# LDC10.net
KiCad netlist of a schematic drawn in Altium Designer
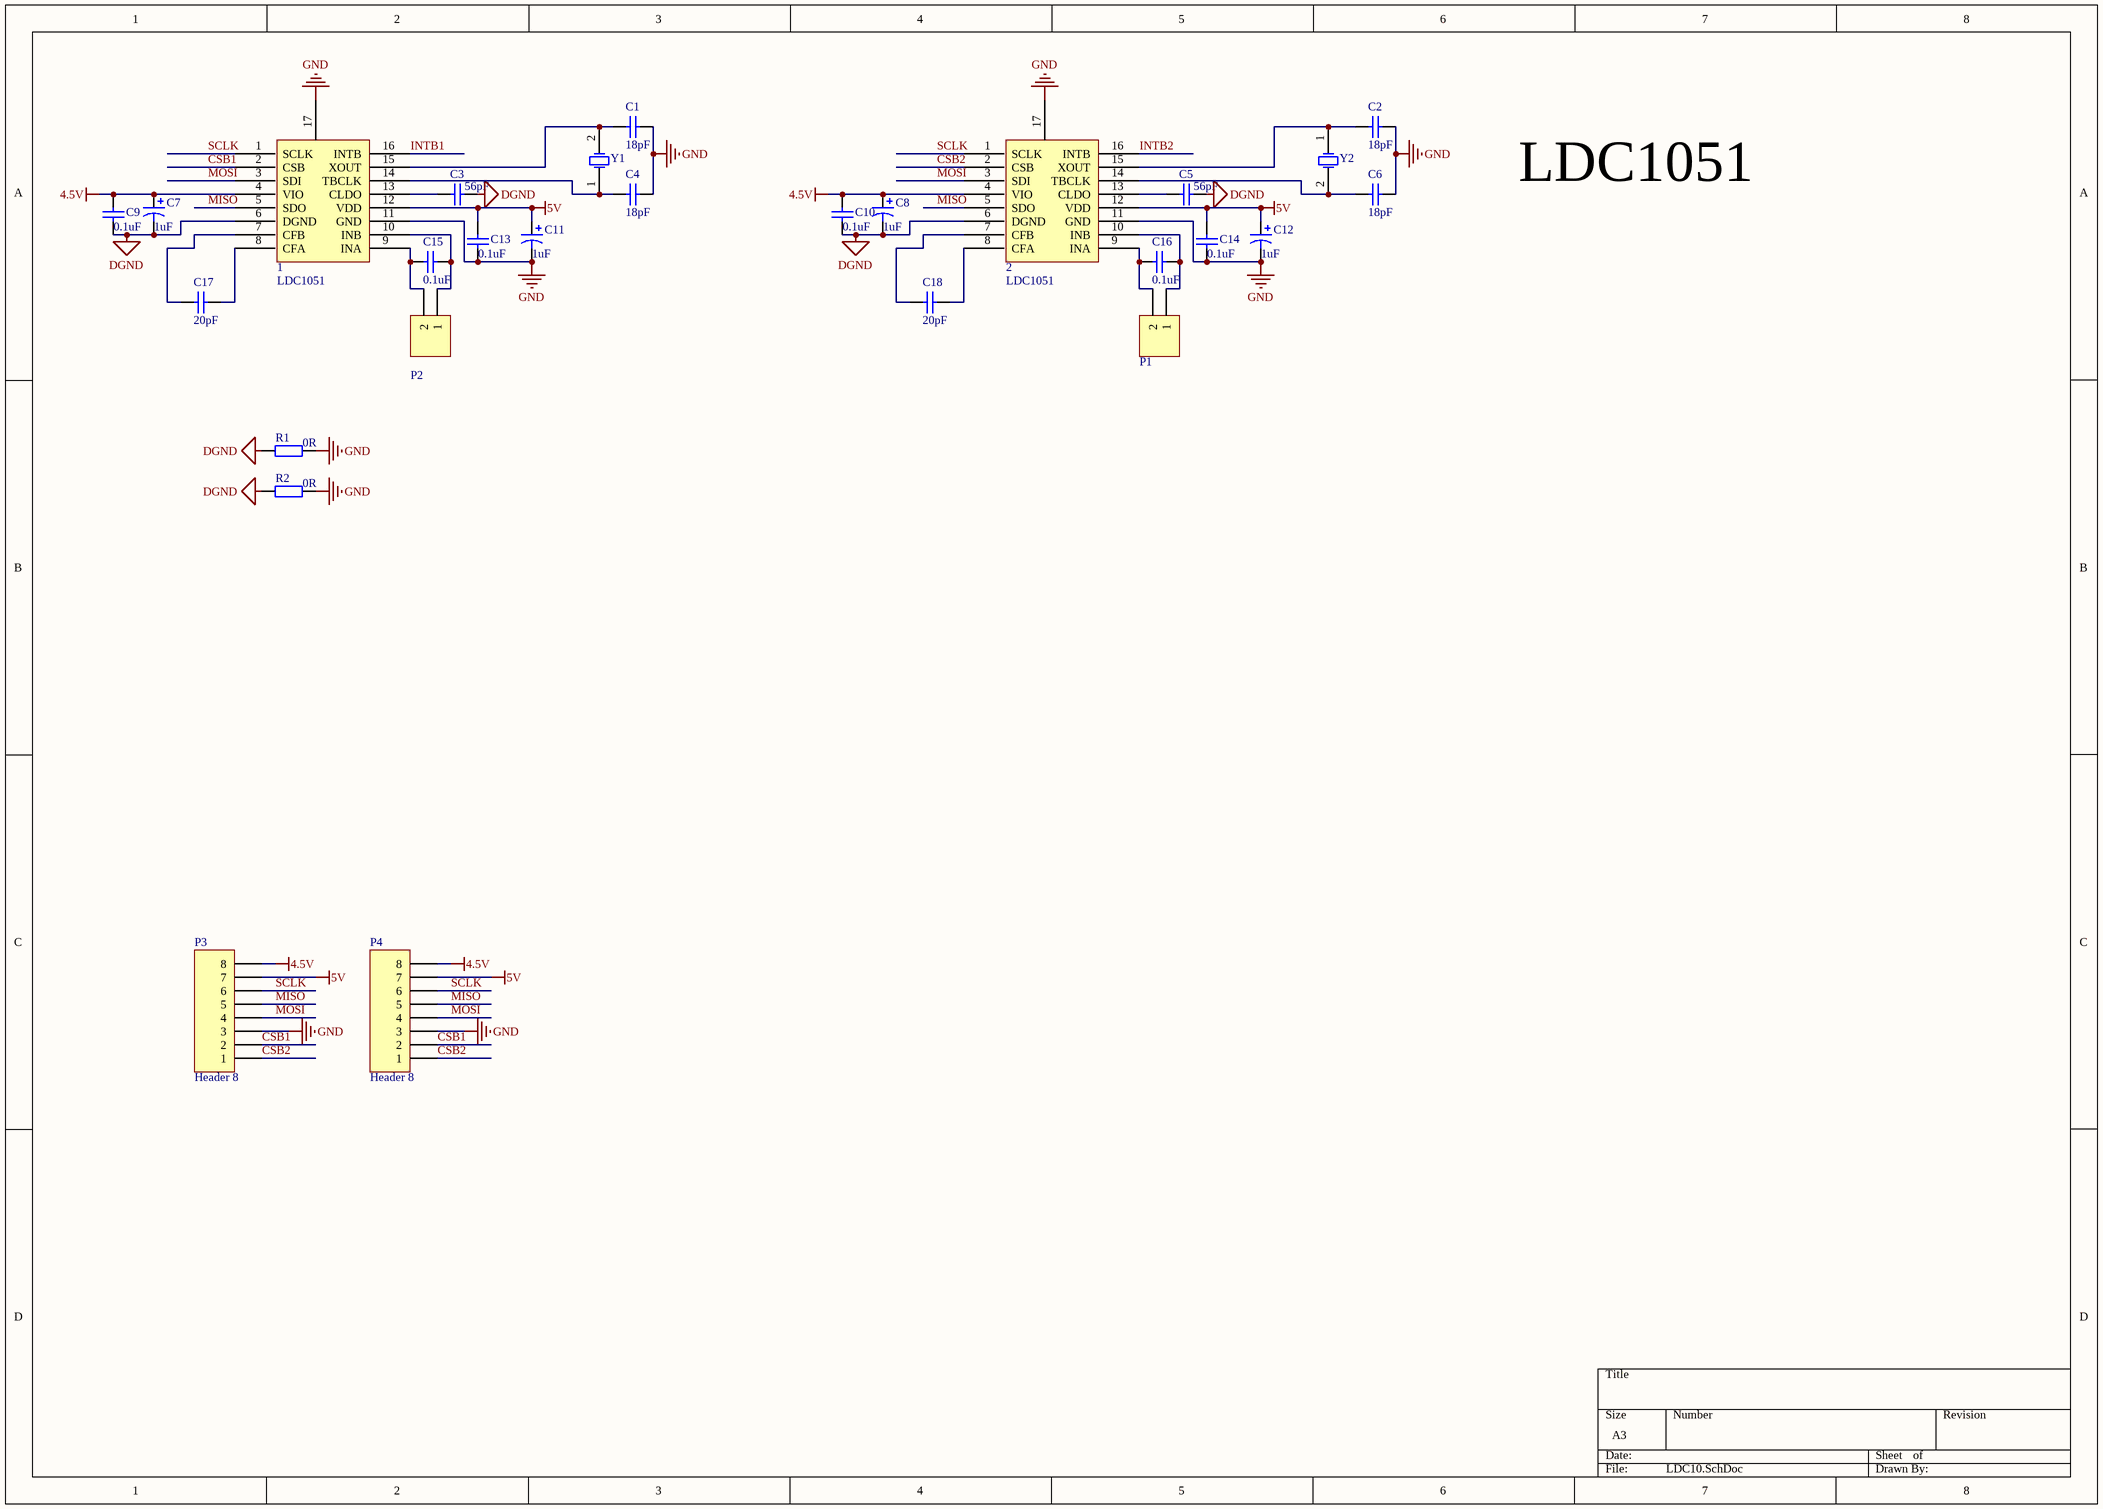
[diagram p0: LDC10.SchDoc]

(export (version "E")
  (design (tool "Eeschema 10.0.6"))
  (components
    (comp (ref "1") (value "LDC1051") (footprint "LDC1000") (libsource (lib "原理图") (part "LDC1000")))
    (comp (ref "2") (value "LDC1051") (footprint "LDC1000") (libsource (lib "原理图") (part "LDC1000")))
    (comp (ref "C1")
      (value "18pF")
      (footprint "C2012")
      (description "Capacitor")
      (fields (field (name "Comment") "Cap") (field (name "PUBLISHER") "Altium Limited"))
      (libsource (lib "Miscellaneous Devices") (part "Cap"))
    )
    (comp (ref "C2")
      (value "18pF")
      (footprint "C2012")
      (description "Capacitor")
      (fields (field (name "Comment") "Cap") (field (name "PUBLISHER") "Altium Limited"))
      (libsource (lib "Miscellaneous Devices") (part "Cap"))
    )
    (comp (ref "C3")
      (value "56pF")
      (footprint "C2012")
      (description "Capacitor")
      (fields (field (name "Comment") "Cap") (field (name "PUBLISHER") "Altium Limited"))
      (libsource (lib "Miscellaneous Devices") (part "Cap"))
    )
    (comp (ref "C4")
      (value "18pF")
      (footprint "C2012")
      (description "Capacitor")
      (fields (field (name "Comment") "Cap") (field (name "PUBLISHER") "Altium Limited"))
      (libsource (lib "Miscellaneous Devices") (part "Cap"))
    )
    (comp (ref "C5")
      (value "56pF")
      (footprint "C2012")
      (description "Capacitor")
      (fields (field (name "Comment") "Cap") (field (name "PUBLISHER") "Altium Limited"))
      (libsource (lib "Miscellaneous Devices") (part "Cap"))
    )
    (comp (ref "C6")
      (value "18pF")
      (footprint "C2012")
      (description "Capacitor")
      (fields (field (name "Comment") "Cap") (field (name "PUBLISHER") "Altium Limited"))
      (libsource (lib "Miscellaneous Devices") (part "Cap"))
    )
    (comp (ref "C7")
      (value "1uF")
      (footprint "C2012")
      (description "Polarized Capacitor (Radial)")
      (fields (field (name "Comment") "Cap Pol1") (field (name "PUBLISHER") "Altium Limited"))
      (libsource (lib "Miscellaneous Devices") (part "Cap Pol1"))
    )
    (comp (ref "C8")
      (value "1uF")
      (footprint "C2012")
      (description "Polarized Capacitor (Radial)")
      (fields (field (name "Comment") "Cap Pol1") (field (name "PUBLISHER") "Altium Limited"))
      (libsource (lib "Miscellaneous Devices") (part "Cap Pol1"))
    )
    (comp (ref "C9")
      (value "0.1uF")
      (footprint "C2012")
      (description "Capacitor")
      (fields (field (name "Comment") "Cap") (field (name "PUBLISHER") "Altium Limited"))
      (libsource (lib "Miscellaneous Devices") (part "Cap"))
    )
    (comp (ref "C10")
      (value "0.1uF")
      (footprint "C2012")
      (description "Capacitor")
      (fields (field (name "Comment") "Cap") (field (name "PUBLISHER") "Altium Limited"))
      (libsource (lib "Miscellaneous Devices") (part "Cap"))
    )
    (comp (ref "C11")
      (value "1uF")
      (footprint "C2012")
      (description "Polarized Capacitor (Radial)")
      (fields (field (name "Comment") "Cap Pol1") (field (name "PUBLISHER") "Altium Limited"))
      (libsource (lib "Miscellaneous Devices") (part "Cap Pol1"))
    )
    (comp (ref "C12")
      (value "1uF")
      (footprint "C2012")
      (description "Polarized Capacitor (Radial)")
      (fields (field (name "Comment") "Cap Pol1") (field (name "PUBLISHER") "Altium Limited"))
      (libsource (lib "Miscellaneous Devices") (part "Cap Pol1"))
    )
    (comp (ref "C13")
      (value "0.1uF")
      (footprint "C2012")
      (description "Capacitor")
      (fields (field (name "Comment") "Cap") (field (name "PUBLISHER") "Altium Limited"))
      (libsource (lib "Miscellaneous Devices") (part "Cap"))
    )
    (comp (ref "C14")
      (value "0.1uF")
      (footprint "C2012")
      (description "Capacitor")
      (fields (field (name "Comment") "Cap") (field (name "PUBLISHER") "Altium Limited"))
      (libsource (lib "Miscellaneous Devices") (part "Cap"))
    )
    (comp (ref "C15")
      (value "0.1uF")
      (footprint "C2012")
      (description "Capacitor")
      (fields (field (name "Comment") "Cap") (field (name "PUBLISHER") "Altium Limited"))
      (libsource (lib "Miscellaneous Devices") (part "Cap"))
    )
    (comp (ref "C16")
      (value "0.1uF")
      (footprint "C2012")
      (description "Capacitor")
      (fields (field (name "Comment") "Cap") (field (name "PUBLISHER") "Altium Limited"))
      (libsource (lib "Miscellaneous Devices") (part "Cap"))
    )
    (comp (ref "C17")
      (value "20pF")
      (footprint "C2012")
      (description "Capacitor")
      (fields (field (name "Comment") "Cap") (field (name "PUBLISHER") "Altium Limited"))
      (libsource (lib "Miscellaneous Devices") (part "Cap"))
    )
    (comp (ref "C18")
      (value "20pF")
      (footprint "C2012")
      (description "Capacitor")
      (fields (field (name "Comment") "Cap") (field (name "PUBLISHER") "Altium Limited"))
      (libsource (lib "Miscellaneous Devices") (part "Cap"))
    )
    (comp (ref "P1")
      (value "Header 2")
      (footprint "HDR1X2")
      (description "Header, 2-Pin")
      (fields (field (name "PUBLISHER") "Altium Limited"))
      (libsource (lib "Sparks") (part "Header 2"))
    )
    (comp (ref "P2")
      (value "Header 2")
      (footprint "HDR1X2")
      (description "Header, 2-Pin")
      (fields (field (name "PUBLISHER") "Altium Limited"))
      (libsource (lib "Sparks") (part "Header 2"))
    )
    (comp (ref "P3")
      (value "Header 8")
      (footprint "HDR1X8")
      (description "Header, 8-Pin")
      (fields (field (name "PUBLISHER") "Altium Limited"))
      (libsource (lib "Sparks") (part "Header 8"))
    )
    (comp (ref "P4")
      (value "Header 8")
      (footprint "HDR1X8")
      (description "Header, 8-Pin")
      (fields (field (name "PUBLISHER") "Altium Limited"))
      (libsource (lib "Sparks") (part "Header 8"))
    )
    (comp (ref "R1")
      (value "0R")
      (footprint "1206(2)")
      (description "Resistor")
      (fields (field (name "Comment") "Res2") (field (name "PUBLISHER") "Altium Limited"))
      (libsource (lib "Miscellaneous Devices") (part "Res2"))
    )
    (comp (ref "R2")
      (value "0R")
      (footprint "1206(2)")
      (description "Resistor")
      (fields (field (name "Comment") "Res2") (field (name "PUBLISHER") "Altium Limited"))
      (libsource (lib "Miscellaneous Devices") (part "Res2"))
    )
    (comp (ref "Y1")
      (value "XTAL")
      (footprint "XTAL-RAD-0.2")
      (description "晶体振荡器")
      (fields (field (name "PUBLISHER") "Altium Limited"))
      (libsource (lib "Sparks") (part "XTAL"))
    )
    (comp (ref "Y2")
      (value "XTAL")
      (footprint "XTAL-RAD-0.2")
      (description "晶体振荡器")
      (fields (field (name "PUBLISHER") "Altium Limited"))
      (libsource (lib "Sparks") (part "XTAL"))
    )
  )
  (nets
    (net (code "1") (name "/CSB1") (class "Default")
      (node (ref "1") (pin "2") (pinfunction "CSB_2") (pintype "passive"))
      (node (ref "P3") (pin "2") (pinfunction "2_2") (pintype "passive"))
      (node (ref "P4") (pin "2") (pinfunction "2_2") (pintype "passive"))
    )
    (net (code "2") (name "/CSB2") (class "Default")
      (node (ref "2") (pin "2") (pinfunction "CSB_2") (pintype "passive"))
      (node (ref "P3") (pin "1") (pinfunction "1_1") (pintype "passive"))
      (node (ref "P4") (pin "1") (pinfunction "1_1") (pintype "passive"))
    )
    (net (code "3") (name "/INTB1") (class "Default")
      (node (ref "1") (pin "16") (pinfunction "INTB_16") (pintype "passive"))
    )
    (net (code "4") (name "/INTB2") (class "Default")
      (node (ref "2") (pin "16") (pinfunction "INTB_16") (pintype "passive"))
    )
    (net (code "5") (name "/MISO") (class "Default")
      (node (ref "1") (pin "5") (pinfunction "SDO_5") (pintype "passive"))
      (node (ref "2") (pin "5") (pinfunction "SDO_5") (pintype "passive"))
      (node (ref "P3") (pin "5") (pinfunction "5_5") (pintype "passive"))
      (node (ref "P4") (pin "5") (pinfunction "5_5") (pintype "passive"))
    )
    (net (code "6") (name "/MOSI") (class "Default")
      (node (ref "1") (pin "3") (pinfunction "SDI_3") (pintype "passive"))
      (node (ref "2") (pin "3") (pinfunction "SDI_3") (pintype "passive"))
      (node (ref "P3") (pin "4") (pinfunction "4_4") (pintype "passive"))
      (node (ref "P4") (pin "4") (pinfunction "4_4") (pintype "passive"))
    )
    (net (code "7") (name "/SCLK") (class "Default")
      (node (ref "1") (pin "1") (pinfunction "SCLK_1") (pintype "passive"))
      (node (ref "2") (pin "1") (pinfunction "SCLK_1") (pintype "passive"))
      (node (ref "P3") (pin "6") (pinfunction "6_6") (pintype "passive"))
      (node (ref "P4") (pin "6") (pinfunction "6_6") (pintype "passive"))
    )
    (net (code "8") (name "4.5V") (class "Default")
      (node (ref "1") (pin "4") (pinfunction "VIO_4") (pintype "passive"))
      (node (ref "2") (pin "4") (pinfunction "VIO_4") (pintype "passive"))
      (node (ref "C10") (pin "2") (pinfunction "2_2") (pintype "passive"))
      (node (ref "C7") (pin "1") (pinfunction "1_1") (pintype "passive"))
      (node (ref "C8") (pin "1") (pinfunction "1_1") (pintype "passive"))
      (node (ref "C9") (pin "2") (pinfunction "2_2") (pintype "passive"))
      (node (ref "P3") (pin "8") (pinfunction "8_8") (pintype "passive"))
      (node (ref "P4") (pin "8") (pinfunction "8_8") (pintype "passive"))
    )
    (net (code "9") (name "5V") (class "Default")
      (node (ref "1") (pin "12") (pinfunction "VDD_12") (pintype "passive"))
      (node (ref "2") (pin "12") (pinfunction "VDD_12") (pintype "passive"))
      (node (ref "C11") (pin "1") (pinfunction "1_1") (pintype "passive"))
      (node (ref "C12") (pin "1") (pinfunction "1_1") (pintype "passive"))
      (node (ref "C13") (pin "2") (pinfunction "2_2") (pintype "passive"))
      (node (ref "C14") (pin "2") (pinfunction "2_2") (pintype "passive"))
      (node (ref "P3") (pin "7") (pinfunction "7_7") (pintype "passive"))
      (node (ref "P4") (pin "7") (pinfunction "7_7") (pintype "passive"))
    )
    (net (code "10") (name "DGND") (class "Default")
      (node (ref "1") (pin "6") (pinfunction "DGND_6") (pintype "passive"))
      (node (ref "2") (pin "6") (pinfunction "DGND_6") (pintype "passive"))
      (node (ref "C10") (pin "1") (pinfunction "1_1") (pintype "passive"))
      (node (ref "C3") (pin "1") (pinfunction "1_1") (pintype "passive"))
      (node (ref "C5") (pin "1") (pinfunction "1_1") (pintype "passive"))
      (node (ref "C7") (pin "2") (pinfunction "2_2") (pintype "passive"))
      (node (ref "C8") (pin "2") (pinfunction "2_2") (pintype "passive"))
      (node (ref "C9") (pin "1") (pinfunction "1_1") (pintype "passive"))
      (node (ref "R1") (pin "2") (pinfunction "2_2") (pintype "passive"))
      (node (ref "R2") (pin "2") (pinfunction "2_2") (pintype "passive"))
    )
    (net (code "11") (name "GND") (class "Default")
      (node (ref "1") (pin "11") (pinfunction "GND_11") (pintype "passive"))
      (node (ref "1") (pin "17") (pinfunction "GND_17") (pintype "passive"))
      (node (ref "2") (pin "11") (pinfunction "GND_11") (pintype "passive"))
      (node (ref "2") (pin "17") (pinfunction "GND_17") (pintype "passive"))
      (node (ref "C1") (pin "1") (pinfunction "1_1") (pintype "passive"))
      (node (ref "C11") (pin "2") (pinfunction "2_2") (pintype "passive"))
      (node (ref "C12") (pin "2") (pinfunction "2_2") (pintype "passive"))
      (node (ref "C13") (pin "1") (pinfunction "1_1") (pintype "passive"))
      (node (ref "C14") (pin "1") (pinfunction "1_1") (pintype "passive"))
      (node (ref "C2") (pin "1") (pinfunction "1_1") (pintype "passive"))
      (node (ref "C4") (pin "1") (pinfunction "1_1") (pintype "passive"))
      (node (ref "C6") (pin "1") (pinfunction "1_1") (pintype "passive"))
      (node (ref "P3") (pin "3") (pinfunction "3_3") (pintype "passive"))
      (node (ref "P4") (pin "3") (pinfunction "3_3") (pintype "passive"))
      (node (ref "R1") (pin "1") (pinfunction "1_1") (pintype "passive"))
      (node (ref "R2") (pin "1") (pinfunction "1_1") (pintype "passive"))
    )
    (net (code "12") (name "Net-(1-CFA)") (class "Default")
      (node (ref "1") (pin "8") (pinfunction "CFA_8") (pintype "passive"))
      (node (ref "C17") (pin "1") (pinfunction "1_1") (pintype "passive"))
    )
    (net (code "13") (name "Net-(1-CFB)") (class "Default")
      (node (ref "1") (pin "7") (pinfunction "CFB_7") (pintype "passive"))
      (node (ref "C17") (pin "2") (pinfunction "2_2") (pintype "passive"))
    )
    (net (code "14") (name "Net-(1-CLDO)") (class "Default")
      (node (ref "1") (pin "13") (pinfunction "CLDO_13") (pintype "passive"))
      (node (ref "C3") (pin "2") (pinfunction "2_2") (pintype "passive"))
    )
    (net (code "15") (name "Net-(1-INA)") (class "Default")
      (node (ref "1") (pin "9") (pinfunction "INA_9") (pintype "passive"))
      (node (ref "C15") (pin "2") (pinfunction "2_2") (pintype "passive"))
      (node (ref "P2") (pin "2") (pinfunction "2_2") (pintype "passive"))
    )
    (net (code "16") (name "Net-(1-INB)") (class "Default")
      (node (ref "1") (pin "10") (pinfunction "INB_10") (pintype "passive"))
      (node (ref "C15") (pin "1") (pinfunction "1_1") (pintype "passive"))
      (node (ref "P2") (pin "1") (pinfunction "1_1") (pintype "passive"))
    )
    (net (code "17") (name "Net-(1-TBCLK)") (class "Default")
      (node (ref "1") (pin "14") (pinfunction "TBCLK_14") (pintype "passive"))
      (node (ref "C4") (pin "2") (pinfunction "2_2") (pintype "passive"))
      (node (ref "Y1") (pin "1") (pinfunction "OSC1_1") (pintype "passive"))
    )
    (net (code "18") (name "Net-(1-XOUT)") (class "Default")
      (node (ref "1") (pin "15") (pinfunction "XOUT_15") (pintype "passive"))
      (node (ref "C1") (pin "2") (pinfunction "2_2") (pintype "passive"))
      (node (ref "Y1") (pin "2") (pinfunction "OSC2_2") (pintype "passive"))
    )
    (net (code "19") (name "Net-(2-CFA)") (class "Default")
      (node (ref "2") (pin "8") (pinfunction "CFA_8") (pintype "passive"))
      (node (ref "C18") (pin "1") (pinfunction "1_1") (pintype "passive"))
    )
    (net (code "20") (name "Net-(2-CFB)") (class "Default")
      (node (ref "2") (pin "7") (pinfunction "CFB_7") (pintype "passive"))
      (node (ref "C18") (pin "2") (pinfunction "2_2") (pintype "passive"))
    )
    (net (code "21") (name "Net-(2-CLDO)") (class "Default")
      (node (ref "2") (pin "13") (pinfunction "CLDO_13") (pintype "passive"))
      (node (ref "C5") (pin "2") (pinfunction "2_2") (pintype "passive"))
    )
    (net (code "22") (name "Net-(2-INA)") (class "Default")
      (node (ref "2") (pin "9") (pinfunction "INA_9") (pintype "passive"))
      (node (ref "C16") (pin "2") (pinfunction "2_2") (pintype "passive"))
      (node (ref "P1") (pin "2") (pinfunction "2_2") (pintype "passive"))
    )
    (net (code "23") (name "Net-(2-INB)") (class "Default")
      (node (ref "2") (pin "10") (pinfunction "INB_10") (pintype "passive"))
      (node (ref "C16") (pin "1") (pinfunction "1_1") (pintype "passive"))
      (node (ref "P1") (pin "1") (pinfunction "1_1") (pintype "passive"))
    )
    (net (code "24") (name "Net-(2-TBCLK)") (class "Default")
      (node (ref "2") (pin "14") (pinfunction "TBCLK_14") (pintype "passive"))
      (node (ref "C6") (pin "2") (pinfunction "2_2") (pintype "passive"))
      (node (ref "Y2") (pin "2") (pinfunction "OSC2_2") (pintype "passive"))
    )
    (net (code "25") (name "Net-(2-XOUT)") (class "Default")
      (node (ref "2") (pin "15") (pinfunction "XOUT_15") (pintype "passive"))
      (node (ref "C2") (pin "2") (pinfunction "2_2") (pintype "passive"))
      (node (ref "Y2") (pin "1") (pinfunction "OSC1_1") (pintype "passive"))
    )
  )
)
